# 5vBuck.net
KiCad netlist of a schematic drawn in EAGLE
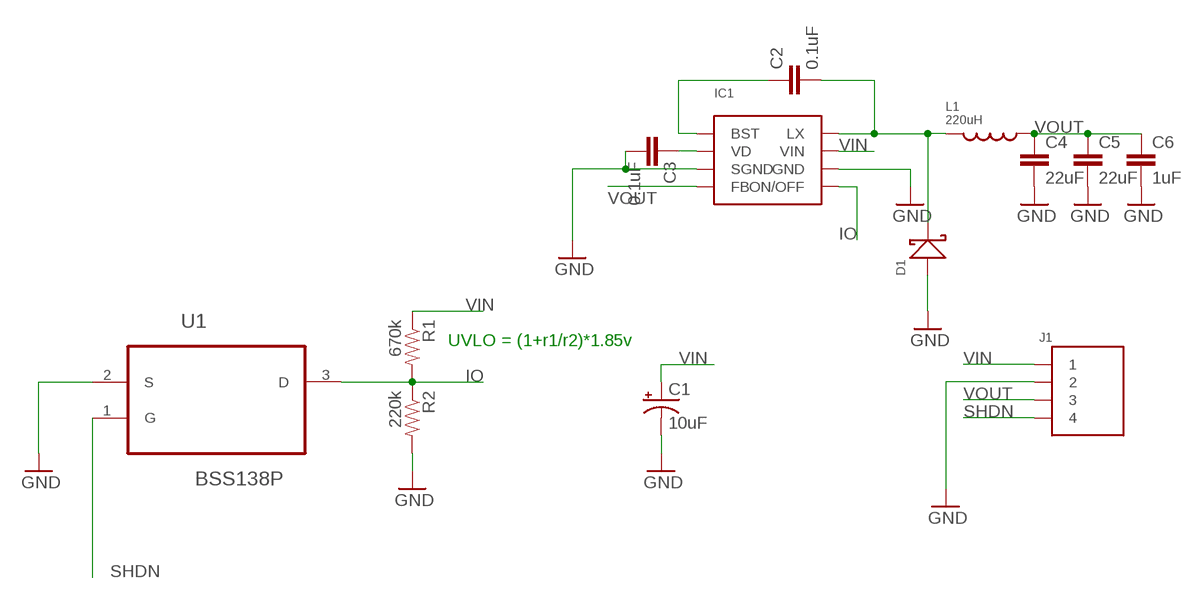
[diagram p0: schematic, sheet 1]

(export (version "E")
  (design (tool "Eeschema 10.0.6"))
  (components
    (comp (ref "C1")
      (value "10uF")
      (footprint "eagle-import:NIPPON_F80")
      (libsource (lib "eagle-import") (part "CAP_POLF80"))
    )
    (comp (ref "C2")
      (value "0.1uF")
      (footprint "eagle-import:0805-CAP")
      (libsource (lib "eagle-import") (part "0.33UF-50V-10%(0805)"))
    )
    (comp (ref "C3")
      (value "0.1uF")
      (footprint "eagle-import:0805-CAP")
      (libsource (lib "eagle-import") (part "0.33UF-50V-10%(0805)"))
    )
    (comp (ref "C4")
      (value "22uF")
      (footprint "eagle-import:0805-CAP")
      (libsource (lib "eagle-import") (part "0.33UF-50V-10%(0805)"))
    )
    (comp (ref "C5")
      (value "22uF")
      (footprint "eagle-import:0805-CAP")
      (libsource (lib "eagle-import") (part "0.33UF-50V-10%(0805)"))
    )
    (comp (ref "C6")
      (value "1uF")
      (footprint "eagle-import:0805-CAP")
      (libsource (lib "eagle-import") (part "0.33UF-50V-10%(0805)"))
    )
    (comp (ref "D1")
      (value "DIODE_SCHOTTKYSOD-123")
      (footprint "eagle-import:SOD-123")
      (libsource (lib "eagle-import") (part "DIODE_SCHOTTKYSOD-123"))
    )
    (comp (ref "IC1")
      (value "M5033")
      (footprint "eagle-import:SOIC-8")
      (libsource (lib "eagle-import") (part "M5033"))
    )
    (comp (ref "J1")
      (value "CONNECTOR_4PIN")
      (footprint "eagle-import:4PIN_.1'")
      (libsource (lib "eagle-import") (part "CONNECTOR_4PIN"))
    )
    (comp (ref "L1")
      (value "220uH")
      (footprint "eagle-import:6X6MM_IND")
      (libsource (lib "eagle-import") (part "CHIP_IND1"))
    )
    (comp (ref "R1")
      (value "670k")
      (footprint "eagle-import:0805")
      (libsource (lib "eagle-import") (part "0.22OHM-1/4W-1%(0805)"))
    )
    (comp (ref "R2")
      (value "220k")
      (footprint "eagle-import:0805")
      (libsource (lib "eagle-import") (part "0.22OHM-1/4W-1%(0805)"))
    )
    (comp (ref "U1")
      (value "BSS138P")
      (footprint "eagle-import:SOT95P230X110-3N")
      (libsource (lib "eagle-import") (part "BSS138P"))
    )
  )
  (nets
    (net (code "1") (name "/IO") (class "Default")
      (node (ref "IC1") (pin "P$5") (pinfunction "ON/OFF_P$5") (pintype "bidirectional"))
      (node (ref "R1") (pin "2") (pinfunction "2_2") (pintype "passive"))
      (node (ref "R2") (pin "1") (pinfunction "1_1") (pintype "passive"))
      (node (ref "U1") (pin "3") (pinfunction "D_3") (pintype "passive"))
    )
    (net (code "2") (name "/SHDN") (class "Default")
      (node (ref "J1") (pin "P$4") (pinfunction "4_P$4") (pintype "bidirectional"))
      (node (ref "U1") (pin "1") (pinfunction "G_1") (pintype "passive"))
    )
    (net (code "3") (name "/VIN") (class "Default")
      (node (ref "C1") (pin "+") (pinfunction "+_+") (pintype "passive"))
      (node (ref "IC1") (pin "P$7") (pinfunction "VIN_P$7") (pintype "bidirectional"))
      (node (ref "J1") (pin "P$1") (pinfunction "1_P$1") (pintype "bidirectional"))
      (node (ref "R1") (pin "1") (pinfunction "1_1") (pintype "passive"))
    )
    (net (code "4") (name "/VOUT") (class "Default")
      (node (ref "C4") (pin "1") (pinfunction "1_1") (pintype "passive"))
      (node (ref "C5") (pin "1") (pinfunction "1_1") (pintype "passive"))
      (node (ref "C6") (pin "1") (pinfunction "1_1") (pintype "passive"))
      (node (ref "IC1") (pin "P$4") (pinfunction "FB_P$4") (pintype "bidirectional"))
      (node (ref "J1") (pin "P$3") (pinfunction "3_P$3") (pintype "bidirectional"))
      (node (ref "L1") (pin "P$2") (pinfunction "P$2_P$2") (pintype "bidirectional"))
    )
    (net (code "5") (name "GND") (class "Default")
      (node (ref "C1") (pin "-") (pinfunction "-_-") (pintype "passive"))
      (node (ref "C3") (pin "2") (pinfunction "2_2") (pintype "passive"))
      (node (ref "C4") (pin "2") (pinfunction "2_2") (pintype "passive"))
      (node (ref "C5") (pin "2") (pinfunction "2_2") (pintype "passive"))
      (node (ref "C6") (pin "2") (pinfunction "2_2") (pintype "passive"))
      (node (ref "D1") (pin "ANODE") (pinfunction "ANODE_ANODE") (pintype "bidirectional"))
      (node (ref "IC1") (pin "P$3") (pinfunction "SGND_P$3") (pintype "bidirectional"))
      (node (ref "IC1") (pin "P$6") (pinfunction "GND_P$6") (pintype "bidirectional"))
      (node (ref "J1") (pin "P$2") (pinfunction "2_P$2") (pintype "bidirectional"))
      (node (ref "R2") (pin "2") (pinfunction "2_2") (pintype "passive"))
      (node (ref "U1") (pin "2") (pinfunction "S_2") (pintype "passive"))
    )
    (net (code "6") (name "Net-(IC1-BST)") (class "Default")
      (node (ref "C2") (pin "1") (pinfunction "1_1") (pintype "passive"))
      (node (ref "IC1") (pin "P$1") (pinfunction "BST_P$1") (pintype "bidirectional"))
    )
    (net (code "7") (name "Net-(IC1-LX)") (class "Default")
      (node (ref "C2") (pin "2") (pinfunction "2_2") (pintype "passive"))
      (node (ref "D1") (pin "CATHODE") (pinfunction "CATHODE_CATHODE") (pintype "bidirectional"))
      (node (ref "IC1") (pin "P$8") (pinfunction "LX_P$8") (pintype "bidirectional"))
      (node (ref "L1") (pin "P$1") (pinfunction "P$1_P$1") (pintype "bidirectional"))
    )
    (net (code "8") (name "Net-(IC1-VD)") (class "Default")
      (node (ref "C3") (pin "1") (pinfunction "1_1") (pintype "passive"))
      (node (ref "IC1") (pin "P$2") (pinfunction "VD_P$2") (pintype "bidirectional"))
    )
  )
)
